# cp2102.net
KiCad netlist of a schematic drawn in Altium Designer
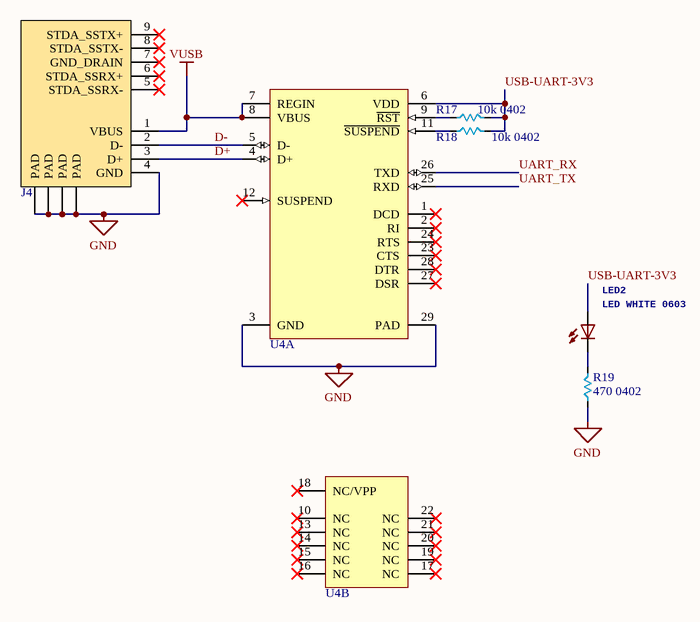
[diagram p0: cp2102.SchDoc]

(export (version "E")
  (design (tool "Eeschema 10.0.6"))
  (components
    (comp (ref "J4")
      (value "0483930003")
      (footprint "robot-cortex:0483930003")
      (description "Conn USB Type A F 9 POS 2mm/2.5mm Solder RA Thru-Hole 9 Terminal 1 Port Embossed T/R")
      (fields (field (name "MANUFACTURER") "Molex"))
      (libsource (lib "robot-cortex") (part "0483930003"))
    )
    (comp (ref "LED2")
      (value "LED WHITE 0603")
      (footprint "LED_0603")
      (description "LED   Source: http://www.osram.convergy.de   Source: www.luxeon.com   Source: www.kingbright.com")
      (fields
        (field (name "MANUFACTURER") "Dialight")
        (field (name "MANUFACTURER PART NUMBER") "5988070107F")
      )
      (libsource (lib "robot-cortex") (part "LED_ESML0603"))
    )
    (comp (ref "R17")
      (value "10k 0402")
      (footprint "R0402")
      (libsource (lib "robot-cortex") (part "R-10k-0402"))
    )
    (comp (ref "R18")
      (value "10k 0402")
      (footprint "R0402")
      (libsource (lib "robot-cortex") (part "R-10k-0402"))
    )
    (comp (ref "R19")
      (value "470 0402")
      (footprint "R0402")
      (fields
        (field (name "MANUFACTURER") "Yageo")
        (field (name "MANUFACTURER PART NUMBER") "RC0402JR-07470RL")
        (field (name "TOLERANCE") "5%")
      )
      (libsource (lib "robot-cortex") (part "R-470-0402"))
    )
    (comp (ref "U4")
      (value "CP2102-GM")
      (footprint "QFN28")
      (description "USB-UART Bridge")
      (libsource (lib "robot-cortex") (part "CP2102-GM"))
    )
  )
  (nets
    (net (code "1") (name "/D+") (class "Default")
      (node (ref "J4") (pin "3") (pinfunction "D+_3") (pintype "passive"))
      (node (ref "U4") (pin "4") (pinfunction "D+_4") (pintype "bidirectional"))
    )
    (net (code "2") (name "/D-") (class "Default")
      (node (ref "J4") (pin "2") (pinfunction "D-_2") (pintype "passive"))
      (node (ref "U4") (pin "5") (pinfunction "D-_5") (pintype "bidirectional"))
    )
    (net (code "3") (name "/UART_RX") (class "Default")
      (node (ref "U4") (pin "26") (pinfunction "TXD_26") (pintype "bidirectional"))
    )
    (net (code "4") (name "/UART_TX") (class "Default")
      (node (ref "U4") (pin "25") (pinfunction "RXD_25") (pintype "bidirectional"))
    )
    (net (code "5") (name "/USB-UART-3V3") (class "Default")
      (node (ref "LED2") (pin "A") (pinfunction "A_A") (pintype "passive"))
      (node (ref "R17") (pin "1") (pinfunction "1_1") (pintype "passive"))
      (node (ref "R18") (pin "1") (pinfunction "1_1") (pintype "passive"))
      (node (ref "U4") (pin "6") (pinfunction "VDD_6") (pintype "power_in"))
    )
    (net (code "6") (name "GND") (class "Default")
      (node (ref "J4") (pin "10") (pinfunction "PAD_10") (pintype "passive"))
      (node (ref "J4") (pin "11") (pinfunction "PAD_11") (pintype "passive"))
      (node (ref "J4") (pin "12") (pinfunction "PAD_12") (pintype "passive"))
      (node (ref "J4") (pin "13") (pinfunction "PAD_13") (pintype "passive"))
      (node (ref "J4") (pin "4") (pinfunction "GND_4") (pintype "passive"))
      (node (ref "R19") (pin "2") (pinfunction "2_2") (pintype "passive"))
      (node (ref "U4") (pin "29") (pinfunction "PAD_29") (pintype "power_in"))
      (node (ref "U4") (pin "3") (pinfunction "GND_3") (pintype "power_in"))
    )
    (net (code "7") (name "Net-(LED2-PadC)") (class "Default")
      (node (ref "LED2") (pin "C") (pinfunction "C_C") (pintype "passive"))
      (node (ref "R19") (pin "1") (pinfunction "1_1") (pintype "passive"))
    )
    (net (code "8") (name "Net-(U4A-~{RST})") (class "Default")
      (node (ref "R17") (pin "2") (pinfunction "2_2") (pintype "passive"))
      (node (ref "U4") (pin "9") (pinfunction "~{RST}_9") (pintype "input"))
    )
    (net (code "9") (name "Net-(U4A-~{SUSPEND})") (class "Default")
      (node (ref "R18") (pin "2") (pinfunction "2_2") (pintype "passive"))
      (node (ref "U4") (pin "11") (pinfunction "~{SUSPEND}_11") (pintype "input"))
    )
    (net (code "10") (name "VUSB") (class "Default")
      (node (ref "J4") (pin "1") (pinfunction "VBUS_1") (pintype "passive"))
      (node (ref "U4") (pin "7") (pinfunction "REGIN_7") (pintype "power_in"))
      (node (ref "U4") (pin "8") (pinfunction "VBUS_8") (pintype "power_in"))
    )
    (net (code "11") (name "unconnected-(J4-GND_DRAIN-Pad7)") (class "Default")
      (node (ref "J4") (pin "7") (pinfunction "GND_DRAIN_7") (pintype "passive+no_connect"))
    )
    (net (code "12") (name "unconnected-(J4-STDA_SSRX+-Pad6)") (class "Default")
      (node (ref "J4") (pin "6") (pinfunction "STDA_SSRX+_6") (pintype "passive+no_connect"))
    )
    (net (code "13") (name "unconnected-(J4-STDA_SSRX--Pad5)") (class "Default")
      (node (ref "J4") (pin "5") (pinfunction "STDA_SSRX-_5") (pintype "passive+no_connect"))
    )
    (net (code "14") (name "unconnected-(J4-STDA_SSTX+-Pad9)") (class "Default")
      (node (ref "J4") (pin "9") (pinfunction "STDA_SSTX+_9") (pintype "passive+no_connect"))
    )
    (net (code "15") (name "unconnected-(J4-STDA_SSTX--Pad8)") (class "Default")
      (node (ref "J4") (pin "8") (pinfunction "STDA_SSTX-_8") (pintype "passive+no_connect"))
    )
    (net (code "16") (name "unconnected-(U4A-CTS-Pad23)") (class "Default")
      (node (ref "U4") (pin "23") (pinfunction "CTS_23") (pintype "power_in+no_connect"))
    )
    (net (code "17") (name "unconnected-(U4A-DCD-Pad1)") (class "Default")
      (node (ref "U4") (pin "1") (pinfunction "DCD_1") (pintype "power_in+no_connect"))
    )
    (net (code "18") (name "unconnected-(U4A-DSR-Pad27)") (class "Default")
      (node (ref "U4") (pin "27") (pinfunction "DSR_27") (pintype "power_in+no_connect"))
    )
    (net (code "19") (name "unconnected-(U4A-DTR-Pad28)") (class "Default")
      (node (ref "U4") (pin "28") (pinfunction "DTR_28") (pintype "power_in+no_connect"))
    )
    (net (code "20") (name "unconnected-(U4A-RI-Pad2)") (class "Default")
      (node (ref "U4") (pin "2") (pinfunction "RI_2") (pintype "power_in+no_connect"))
    )
    (net (code "21") (name "unconnected-(U4A-RTS-Pad24)") (class "Default")
      (node (ref "U4") (pin "24") (pinfunction "RTS_24") (pintype "power_in+no_connect"))
    )
    (net (code "22") (name "unconnected-(U4A-SUSPEND-Pad12)") (class "Default")
      (node (ref "U4") (pin "12") (pinfunction "SUSPEND_12") (pintype "input+no_connect"))
    )
    (net (code "23") (name "unconnected-(U4B-NC-Pad10)") (class "Default")
      (node (ref "U4") (pin "10") (pinfunction "NC_10") (pintype "power_in+no_connect"))
    )
    (net (code "24") (name "unconnected-(U4B-NC-Pad13)") (class "Default")
      (node (ref "U4") (pin "13") (pinfunction "NC_13") (pintype "power_in+no_connect"))
    )
    (net (code "25") (name "unconnected-(U4B-NC-Pad14)") (class "Default")
      (node (ref "U4") (pin "14") (pinfunction "NC_14") (pintype "power_in+no_connect"))
    )
    (net (code "26") (name "unconnected-(U4B-NC-Pad15)") (class "Default")
      (node (ref "U4") (pin "15") (pinfunction "NC_15") (pintype "power_in+no_connect"))
    )
    (net (code "27") (name "unconnected-(U4B-NC-Pad16)") (class "Default")
      (node (ref "U4") (pin "16") (pinfunction "NC_16") (pintype "power_in+no_connect"))
    )
    (net (code "28") (name "unconnected-(U4B-NC-Pad17)") (class "Default")
      (node (ref "U4") (pin "17") (pinfunction "NC_17") (pintype "power_in+no_connect"))
    )
    (net (code "29") (name "unconnected-(U4B-NC-Pad19)") (class "Default")
      (node (ref "U4") (pin "19") (pinfunction "NC_19") (pintype "power_in+no_connect"))
    )
    (net (code "30") (name "unconnected-(U4B-NC-Pad20)") (class "Default")
      (node (ref "U4") (pin "20") (pinfunction "NC_20") (pintype "power_in+no_connect"))
    )
    (net (code "31") (name "unconnected-(U4B-NC-Pad21)") (class "Default")
      (node (ref "U4") (pin "21") (pinfunction "NC_21") (pintype "power_in+no_connect"))
    )
    (net (code "32") (name "unconnected-(U4B-NC-Pad22)") (class "Default")
      (node (ref "U4") (pin "22") (pinfunction "NC_22") (pintype "power_in+no_connect"))
    )
    (net (code "33") (name "unconnected-(U4B-NC{slash}VPP-Pad18)") (class "Default")
      (node (ref "U4") (pin "18") (pinfunction "NC/VPP_18") (pintype "power_in+no_connect"))
    )
  )
)
